# DB.net
KiCad netlist of a schematic drawn in Altium Designer
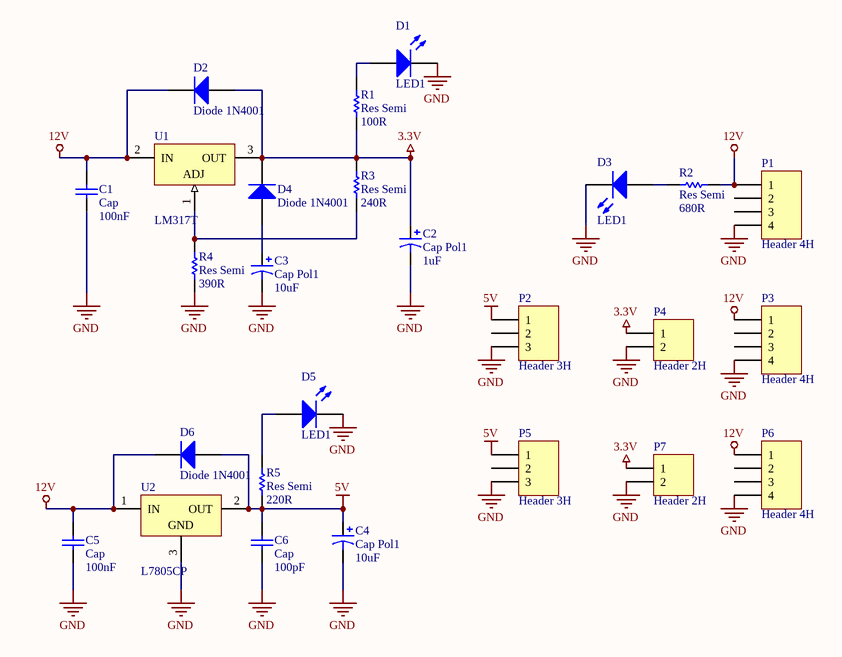
[diagram p0: DB.SchDoc]

(export (version "E")
  (design (tool "Eeschema 10.0.6"))
  (components
    (comp (ref "C1")
      (value "Cap")
      (footprint "CAPR5.08-7.8x3.2")
      (description "Capacitor")
      (fields (field (name "ALTIUM_VALUE") "100nF") (field (name "PUBLISHER") "Altium Limited"))
      (libsource (lib "DB") (part "Cap"))
    )
    (comp (ref "C2")
      (value "Cap Pol1")
      (footprint "CAPPR2-5x6.8")
      (description "Polarized Capacitor (Radial)")
      (fields (field (name "ALTIUM_VALUE") "1uF") (field (name "PUBLISHER") "Altium Limited"))
      (libsource (lib "DB") (part "Cap Pol1"))
    )
    (comp (ref "C3")
      (value "Cap Pol1")
      (footprint "CAPPR2-5x6.8")
      (description "Polarized Capacitor (Radial)")
      (fields (field (name "ALTIUM_VALUE") "10uF") (field (name "PUBLISHER") "Altium Limited"))
      (libsource (lib "DB") (part "Cap Pol1"))
    )
    (comp (ref "C4")
      (value "Cap Pol1")
      (footprint "CAPPR2-5x6.8")
      (description "Polarized Capacitor (Radial)")
      (fields (field (name "ALTIUM_VALUE") "10uF") (field (name "PUBLISHER") "Altium Limited"))
      (libsource (lib "DB") (part "Cap Pol1"))
    )
    (comp (ref "C5")
      (value "Cap")
      (footprint "CAPR5.08-7.8x3.2")
      (description "Capacitor")
      (fields (field (name "ALTIUM_VALUE") "100nF") (field (name "PUBLISHER") "Altium Limited"))
      (libsource (lib "DB") (part "Cap"))
    )
    (comp (ref "C6")
      (value "Cap")
      (footprint "CAPR5.08-7.8x3.2")
      (description "Capacitor")
      (fields (field (name "ALTIUM_VALUE") "100pF") (field (name "PUBLISHER") "Altium Limited"))
      (libsource (lib "DB") (part "Cap"))
    )
    (comp (ref "D1")
      (value "LED1")
      (footprint "LED-1")
      (description "Typical RED GaAs LED")
      (fields (field (name "PUBLISHER") "Altium Limited"))
      (libsource (lib "DB") (part "LED1"))
    )
    (comp (ref "D2")
      (value "Diode 1N4001")
      (footprint "DIO10.46-5.3x2.8")
      (description "1 Amp General Purpose Rectifier")
      (fields (field (name "PUBLISHER") "Altium Limited"))
      (libsource (lib "DB") (part "Diode 1N4007"))
    )
    (comp (ref "D3")
      (value "LED1")
      (footprint "LED-1")
      (description "Typical RED GaAs LED")
      (fields (field (name "PUBLISHER") "Altium Limited"))
      (libsource (lib "DB") (part "LED1"))
    )
    (comp (ref "D4")
      (value "Diode 1N4001")
      (footprint "DIO10.46-5.3x2.8")
      (description "1 Amp General Purpose Rectifier")
      (fields (field (name "PUBLISHER") "Altium Limited"))
      (libsource (lib "DB") (part "Diode 1N4007"))
    )
    (comp (ref "D5")
      (value "LED1")
      (footprint "LED-1")
      (description "Typical RED GaAs LED")
      (fields (field (name "PUBLISHER") "Altium Limited"))
      (libsource (lib "DB") (part "LED1"))
    )
    (comp (ref "D6")
      (value "Diode 1N4001")
      (footprint "DIO10.46-5.3x2.8")
      (description "1 Amp General Purpose Rectifier")
      (fields (field (name "PUBLISHER") "Altium Limited"))
      (libsource (lib "DB") (part "Diode 1N4007"))
    )
    (comp (ref "P1")
      (value "Header 4H")
      (footprint "HDR1X4H")
      (description "Header, 4-Pin, Right Angle")
      (fields (field (name "PUBLISHER") "Altium Limited"))
      (libsource (lib "DB") (part "Header 4H"))
    )
    (comp (ref "P2")
      (value "Header 3H")
      (footprint "HDR1X3H")
      (description "Header, 3-Pin, Right Angle")
      (fields (field (name "PUBLISHER") "Altium Limited"))
      (libsource (lib "DB") (part "Header 3H"))
    )
    (comp (ref "P3")
      (value "Header 4H")
      (footprint "HDR1X4H")
      (description "Header, 4-Pin, Right Angle")
      (fields (field (name "PUBLISHER") "Altium Limited"))
      (libsource (lib "DB") (part "Header 4H"))
    )
    (comp (ref "P4")
      (value "Header 2H")
      (footprint "HDR1X2H")
      (description "Header, 2-Pin, Right Angle")
      (fields (field (name "PUBLISHER") "Altium Limited"))
      (libsource (lib "DB") (part "Header 2H"))
    )
    (comp (ref "P5")
      (value "Header 3H")
      (footprint "HDR1X3H")
      (description "Header, 3-Pin, Right Angle")
      (fields (field (name "PUBLISHER") "Altium Limited"))
      (libsource (lib "DB") (part "Header 3H"))
    )
    (comp (ref "P6")
      (value "Header 4H")
      (footprint "HDR1X4H")
      (description "Header, 4-Pin, Right Angle")
      (fields (field (name "PUBLISHER") "Altium Limited"))
      (libsource (lib "DB") (part "Header 4H"))
    )
    (comp (ref "P7")
      (value "Header 2H")
      (footprint "HDR1X2H")
      (description "Header, 2-Pin, Right Angle")
      (fields (field (name "PUBLISHER") "Altium Limited"))
      (libsource (lib "DB") (part "Header 2H"))
    )
    (comp (ref "R1")
      (value "Res Semi")
      (footprint "RES10-7.8X2.8")
      (description "Semiconductor Resistor")
      (fields (field (name "ALTIUM_VALUE") "100R") (field (name "PUBLISHER") "Altium Limited"))
      (libsource (lib "DB") (part "Res Semi"))
    )
    (comp (ref "R2")
      (value "Res Semi")
      (footprint "RES10-7.8X2.8")
      (description "Semiconductor Resistor")
      (fields (field (name "ALTIUM_VALUE") "680R") (field (name "PUBLISHER") "Altium Limited"))
      (libsource (lib "DB") (part "Res Semi"))
    )
    (comp (ref "R3")
      (value "Res Semi")
      (footprint "RES10-7.8X2.8")
      (description "Semiconductor Resistor")
      (fields (field (name "ALTIUM_VALUE") "240R") (field (name "PUBLISHER") "Altium Limited"))
      (libsource (lib "DB") (part "Res Semi"))
    )
    (comp (ref "R4")
      (value "Res Semi")
      (footprint "RES10-7.8X2.8")
      (description "Semiconductor Resistor")
      (fields (field (name "ALTIUM_VALUE") "390R") (field (name "PUBLISHER") "Altium Limited"))
      (libsource (lib "DB") (part "Res Semi"))
    )
    (comp (ref "R5")
      (value "Res Semi")
      (footprint "RES10-7.8X2.8")
      (description "Semiconductor Resistor")
      (fields (field (name "ALTIUM_VALUE") "220R") (field (name "PUBLISHER") "Altium Limited"))
      (libsource (lib "DB") (part "Res Semi"))
    )
    (comp (ref "U1")
      (value "LM317T")
      (footprint "TO220ABN")
      (description "1.2V to 37V Voltage Regulator")
      (fields (field (name "PUBLISHER") "Altium Limited"))
      (libsource (lib "DB") (part "LM317T"))
    )
    (comp (ref "U2")
      (value "L7805CP")
      (footprint "221A-04")
      (description "Positive Voltage Regulator")
      (fields (field (name "PUBLISHER") "Altium Limited"))
      (libsource (lib "DB") (part "L7805CP"))
    )
  )
  (nets
    (net (code "1") (name "3.3V") (class "Default")
      (node (ref "C2") (pin "1") (pinfunction "1_1") (pintype "passive"))
      (node (ref "D2") (pin "1") (pinfunction "A_1") (pintype "passive"))
      (node (ref "D4") (pin "2") (pinfunction "K_2") (pintype "passive"))
      (node (ref "P4") (pin "1") (pinfunction "1_1") (pintype "passive"))
      (node (ref "P7") (pin "1") (pinfunction "1_1") (pintype "passive"))
      (node (ref "R1") (pin "1") (pinfunction "1_1") (pintype "passive"))
      (node (ref "R3") (pin "2") (pinfunction "2_2") (pintype "passive"))
      (node (ref "U1") (pin "3") (pinfunction "OUT_3") (pintype "power_in"))
    )
    (net (code "2") (name "5V") (class "Default")
      (node (ref "C4") (pin "1") (pinfunction "1_1") (pintype "passive"))
      (node (ref "C6") (pin "1") (pinfunction "1_1") (pintype "passive"))
      (node (ref "D6") (pin "1") (pinfunction "A_1") (pintype "passive"))
      (node (ref "P2") (pin "1") (pinfunction "1_1") (pintype "passive"))
      (node (ref "P5") (pin "1") (pinfunction "1_1") (pintype "passive"))
      (node (ref "R5") (pin "1") (pinfunction "1_1") (pintype "passive"))
      (node (ref "U2") (pin "2") (pinfunction "OUT_2") (pintype "power_in"))
    )
    (net (code "3") (name "12V") (class "Default")
      (node (ref "C1") (pin "1") (pinfunction "1_1") (pintype "passive"))
      (node (ref "C5") (pin "1") (pinfunction "1_1") (pintype "passive"))
      (node (ref "D2") (pin "2") (pinfunction "K_2") (pintype "passive"))
      (node (ref "D6") (pin "2") (pinfunction "K_2") (pintype "passive"))
      (node (ref "P1") (pin "1") (pinfunction "1_1") (pintype "passive"))
      (node (ref "P3") (pin "1") (pinfunction "1_1") (pintype "passive"))
      (node (ref "P6") (pin "1") (pinfunction "1_1") (pintype "passive"))
      (node (ref "R2") (pin "1") (pinfunction "1_1") (pintype "passive"))
      (node (ref "U1") (pin "2") (pinfunction "IN_2") (pintype "power_in"))
      (node (ref "U2") (pin "1") (pinfunction "IN_1") (pintype "power_in"))
    )
    (net (code "4") (name "GND") (class "Default")
      (node (ref "C1") (pin "2") (pinfunction "2_2") (pintype "passive"))
      (node (ref "C2") (pin "2") (pinfunction "2_2") (pintype "passive"))
      (node (ref "C3") (pin "2") (pinfunction "2_2") (pintype "passive"))
      (node (ref "C4") (pin "2") (pinfunction "2_2") (pintype "passive"))
      (node (ref "C5") (pin "2") (pinfunction "2_2") (pintype "passive"))
      (node (ref "C6") (pin "2") (pinfunction "2_2") (pintype "passive"))
      (node (ref "D1") (pin "2") (pinfunction "K_2") (pintype "passive"))
      (node (ref "D3") (pin "2") (pinfunction "K_2") (pintype "passive"))
      (node (ref "D5") (pin "2") (pinfunction "K_2") (pintype "passive"))
      (node (ref "P1") (pin "4") (pinfunction "4_4") (pintype "passive"))
      (node (ref "P2") (pin "3") (pinfunction "3_3") (pintype "passive"))
      (node (ref "P3") (pin "4") (pinfunction "4_4") (pintype "passive"))
      (node (ref "P4") (pin "2") (pinfunction "2_2") (pintype "passive"))
      (node (ref "P5") (pin "3") (pinfunction "3_3") (pintype "passive"))
      (node (ref "P6") (pin "4") (pinfunction "4_4") (pintype "passive"))
      (node (ref "P7") (pin "2") (pinfunction "2_2") (pintype "passive"))
      (node (ref "R4") (pin "1") (pinfunction "1_1") (pintype "passive"))
      (node (ref "U2") (pin "3") (pinfunction "GND_3") (pintype "power_in"))
    )
    (net (code "5") (name "Net-(D1-A)") (class "Default")
      (node (ref "D1") (pin "1") (pinfunction "A_1") (pintype "passive"))
      (node (ref "R1") (pin "2") (pinfunction "2_2") (pintype "passive"))
    )
    (net (code "6") (name "Net-(D3-A)") (class "Default")
      (node (ref "D3") (pin "1") (pinfunction "A_1") (pintype "passive"))
      (node (ref "R2") (pin "2") (pinfunction "2_2") (pintype "passive"))
    )
    (net (code "7") (name "Net-(D4-A)") (class "Default")
      (node (ref "C3") (pin "1") (pinfunction "1_1") (pintype "passive"))
      (node (ref "D4") (pin "1") (pinfunction "A_1") (pintype "passive"))
    )
    (net (code "8") (name "Net-(D5-A)") (class "Default")
      (node (ref "D5") (pin "1") (pinfunction "A_1") (pintype "passive"))
      (node (ref "R5") (pin "2") (pinfunction "2_2") (pintype "passive"))
    )
    (net (code "9") (name "Net-(U1-ADJ)") (class "Default")
      (node (ref "R3") (pin "1") (pinfunction "1_1") (pintype "passive"))
      (node (ref "R4") (pin "2") (pinfunction "2_2") (pintype "passive"))
      (node (ref "U1") (pin "1") (pinfunction "ADJ_1") (pintype "input"))
    )
    (net (code "10") (name "unconnected-(P1-Pad2)") (class "Default")
      (node (ref "P1") (pin "2") (pinfunction "2_2") (pintype "passive"))
    )
    (net (code "11") (name "unconnected-(P1-Pad3)") (class "Default")
      (node (ref "P1") (pin "3") (pinfunction "3_3") (pintype "passive"))
    )
    (net (code "12") (name "unconnected-(P2-Pad2)") (class "Default")
      (node (ref "P2") (pin "2") (pinfunction "2_2") (pintype "passive"))
    )
    (net (code "13") (name "unconnected-(P3-Pad2)") (class "Default")
      (node (ref "P3") (pin "2") (pinfunction "2_2") (pintype "passive"))
    )
    (net (code "14") (name "unconnected-(P3-Pad3)") (class "Default")
      (node (ref "P3") (pin "3") (pinfunction "3_3") (pintype "passive"))
    )
    (net (code "15") (name "unconnected-(P5-Pad2)") (class "Default")
      (node (ref "P5") (pin "2") (pinfunction "2_2") (pintype "passive"))
    )
    (net (code "16") (name "unconnected-(P6-Pad2)") (class "Default")
      (node (ref "P6") (pin "2") (pinfunction "2_2") (pintype "passive"))
    )
    (net (code "17") (name "unconnected-(P6-Pad3)") (class "Default")
      (node (ref "P6") (pin "3") (pinfunction "3_3") (pintype "passive"))
    )
  )
)
